# connectors.net
KiCad netlist of a schematic drawn in Altium Designer
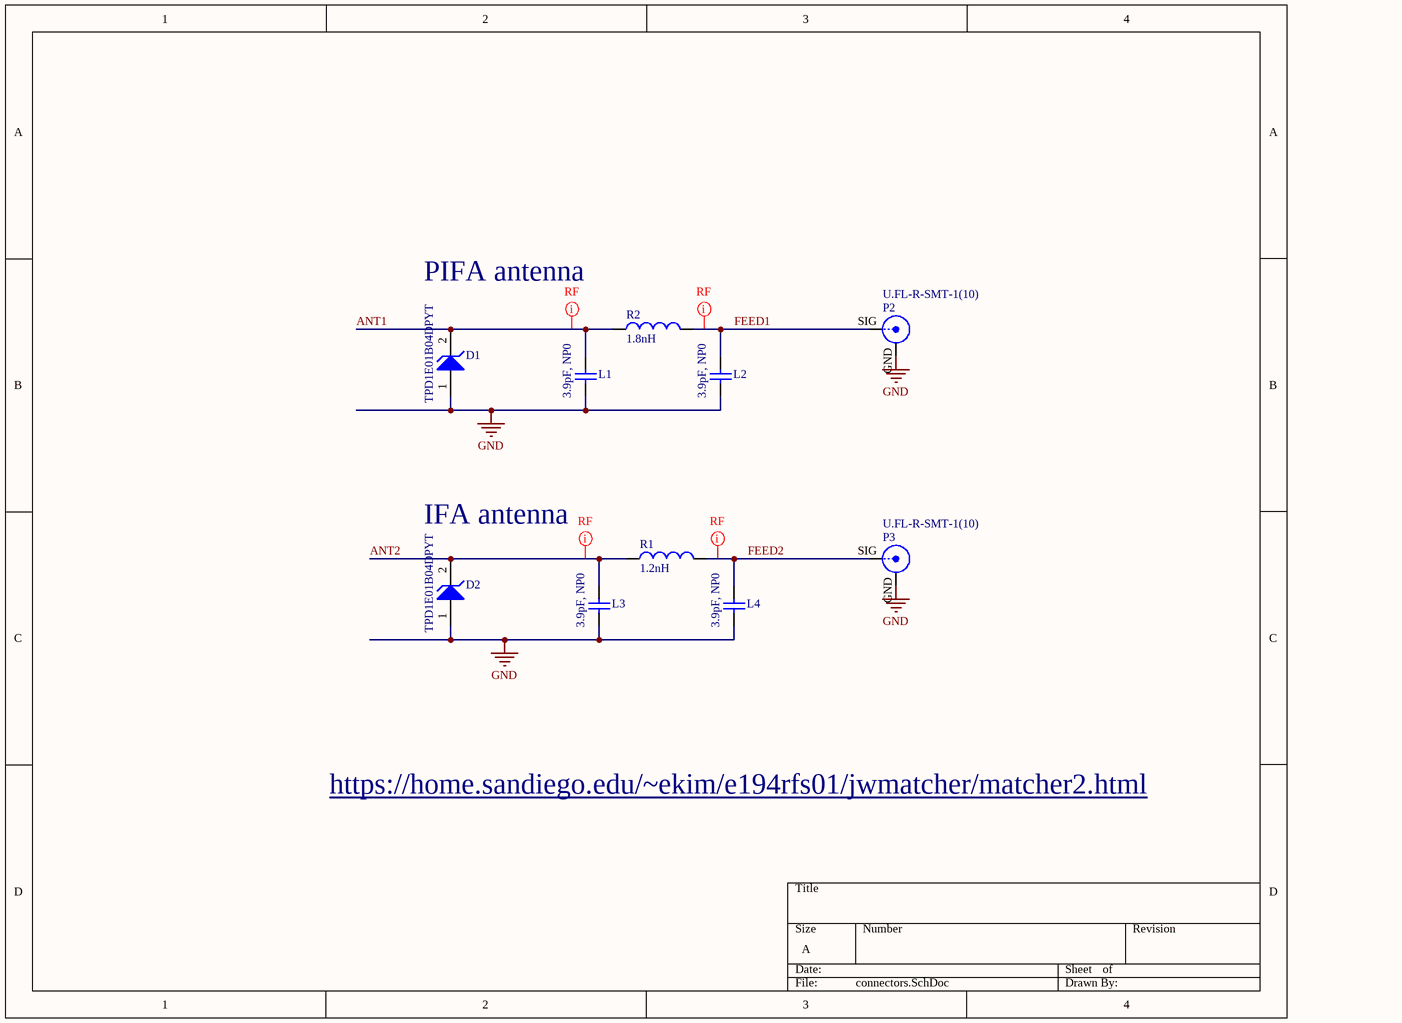
[diagram p0: connectors.SchDoc]

(export (version "E")
  (design (tool "Eeschema 10.0.6"))
  (components
    (comp (ref "D1")
      (value "TPD1E01B04DPYT")
      (footprint "TI_PX1SON-N2")
      (description "CPDUR24V")
      (fields (field (name "PUBLISHER") "Altium Limited"))
      (libsource (lib "Miscellaneous Devices") (part "D Zener"))
    )
    (comp (ref "D2")
      (value "TPD1E01B04DPYT")
      (footprint "TI_PX1SON-N2")
      (description "CPDUR24V")
      (fields (field (name "PUBLISHER") "Altium Limited"))
      (libsource (lib "Miscellaneous Devices") (part "D Zener"))
    )
    (comp (ref "L1")
      (value "3.9pF, NP0")
      (footprint "B_CAP0402")
      (description "Capacitor (Semiconductor SIM Model)")
      (fields (field (name "MPN") "GRM0335C1H3R9BA01D"))
      (libsource (lib "Miscellaneous Devices") (part "Cap Semi"))
    )
    (comp (ref "L2")
      (value "3.9pF, NP0")
      (footprint "B_CAP0402")
      (description "Capacitor (Semiconductor SIM Model)")
      (fields (field (name "MPN") "GRM0335C1H3R9BA01D"))
      (libsource (lib "Miscellaneous Devices") (part "Cap Semi"))
    )
    (comp (ref "L3")
      (value "3.9pF, NP0")
      (footprint "B_CAP0402")
      (description "Capacitor (Semiconductor SIM Model)")
      (fields (field (name "MPN") "GRM0335C1H3R9BA01D"))
      (libsource (lib "Miscellaneous Devices") (part "Cap Semi"))
    )
    (comp (ref "L4")
      (value "3.9pF, NP0")
      (footprint "B_CAP0402")
      (description "Capacitor (Semiconductor SIM Model)")
      (fields (field (name "MPN") "GRM0335C1H3R9BA01D"))
      (libsource (lib "Miscellaneous Devices") (part "Cap Semi"))
    )
    (comp (ref "P2")
      (value "U.FL-R-SMT-1(10)")
      (footprint "HRS_U.FL")
      (description "BNC Elbow Connector")
      (fields (field (name "PUBLISHER") "Altium Limited"))
      (libsource (lib "Miscellaneous Connectors") (part "BNC"))
    )
    (comp (ref "P3")
      (value "U.FL-R-SMT-1(10)")
      (footprint "HRS_U.FL")
      (description "BNC Elbow Connector")
      (fields (field (name "PUBLISHER") "Altium Limited"))
      (libsource (lib "Miscellaneous Connectors") (part "BNC"))
    )
    (comp (ref "R1")
      (value "1.2nH")
      (footprint "B_IND0402")
      (description "Inductor")
      (fields (field (name "MPN") "LQP15MN1N2W02D") (field (name "PUBLISHER") "Altium Limited"))
      (libsource (lib "Miscellaneous Devices") (part "Inductor"))
    )
    (comp (ref "R2")
      (value "1.8nH")
      (footprint "B_IND0402")
      (description "Inductor")
      (fields (field (name "MPN") "LQW15AN1N8C00D") (field (name "PUBLISHER") "Altium Limited"))
      (libsource (lib "Miscellaneous Devices") (part "Inductor"))
    )
  )
  (nets
    (net (code "1") (name "/ANT1") (class "Default")
      (node (ref "D1") (pin "2") (pinfunction "K_2") (pintype "passive"))
      (node (ref "L1") (pin "1") (pinfunction "1_1") (pintype "passive"))
      (node (ref "R2") (pin "1") (pinfunction "1_1") (pintype "passive"))
    )
    (net (code "2") (name "/ANT2") (class "Default")
      (node (ref "D2") (pin "2") (pinfunction "K_2") (pintype "passive"))
      (node (ref "L3") (pin "1") (pinfunction "1_1") (pintype "passive"))
      (node (ref "R1") (pin "1") (pinfunction "1_1") (pintype "passive"))
    )
    (net (code "3") (name "/FEED1") (class "Default")
      (node (ref "L2") (pin "1") (pinfunction "1_1") (pintype "passive"))
      (node (ref "P2") (pin "SIG") (pinfunction "X_SIG") (pintype "passive"))
      (node (ref "R2") (pin "2") (pinfunction "2_2") (pintype "passive"))
    )
    (net (code "4") (name "/FEED2") (class "Default")
      (node (ref "L4") (pin "1") (pinfunction "1_1") (pintype "passive"))
      (node (ref "P3") (pin "SIG") (pinfunction "X_SIG") (pintype "passive"))
      (node (ref "R1") (pin "2") (pinfunction "2_2") (pintype "passive"))
    )
    (net (code "5") (name "GND") (class "Default")
      (node (ref "D1") (pin "1") (pinfunction "A_1") (pintype "passive"))
      (node (ref "D2") (pin "1") (pinfunction "A_1") (pintype "passive"))
      (node (ref "L1") (pin "2") (pinfunction "2_2") (pintype "passive"))
      (node (ref "L2") (pin "2") (pinfunction "2_2") (pintype "passive"))
      (node (ref "L3") (pin "2") (pinfunction "2_2") (pintype "passive"))
      (node (ref "L4") (pin "2") (pinfunction "2_2") (pintype "passive"))
      (node (ref "P2") (pin "GND") (pinfunction "Y_GND") (pintype "passive"))
      (node (ref "P3") (pin "GND") (pinfunction "Y_GND") (pintype "passive"))
    )
  )
)
